# uC.net
KiCad netlist of a schematic drawn in Altium Designer
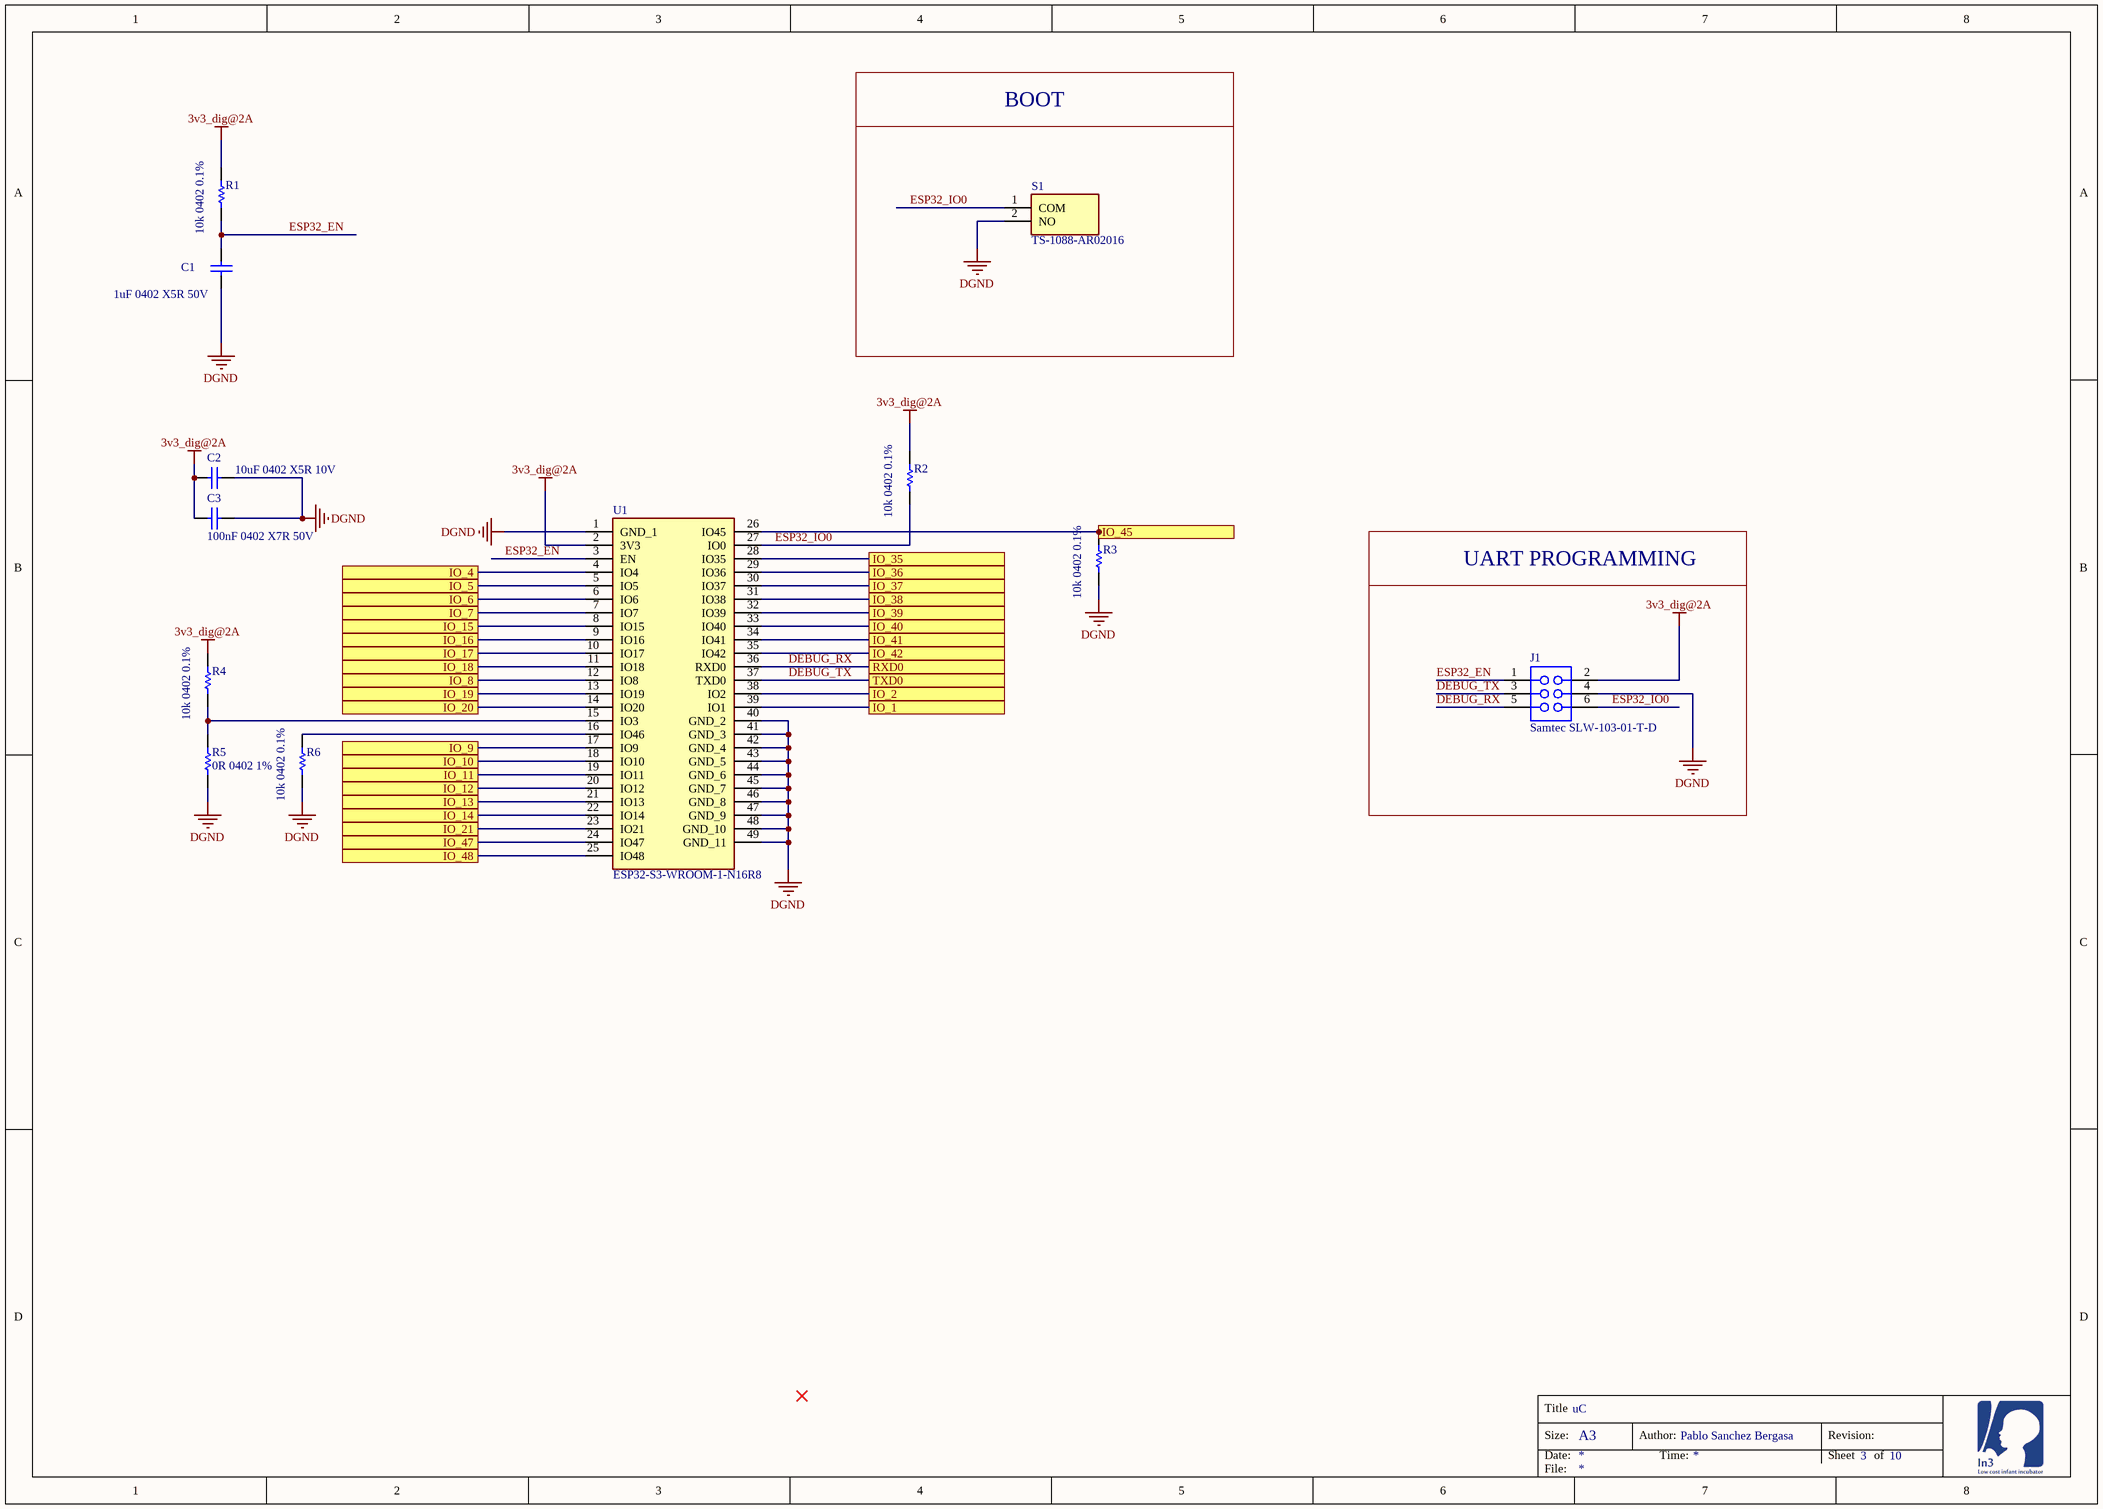
[diagram p0: uC.SchDoc]

(export (version "E")
  (design (tool "Eeschema 10.0.6"))
  (components
    (comp (ref "C1")
      (value "1uF 0402 X5R 50V")
      (footprint "CAPC1005X55X25NL5T10")
      (libsource (lib "Altium Content Vault") (part "CAP-NP-2"))
    )
    (comp (ref "C2")
      (value "10uF 0402 X5R 10V")
      (footprint "CAPC1005X55X25NL5T10")
      (libsource (lib "Altium Content Vault") (part "CAP-NP-2"))
    )
    (comp (ref "C3")
      (value "100nF 0402 X7R 50V")
      (footprint "CAPC1005X55X25NL5T10")
      (libsource (lib "Altium Content Vault") (part "CAP-NP-2"))
    )
    (comp (ref "J1")
      (value "Samtec SLW-103-01-T-D")
      (footprint "PCB-37z8hw1ej4f71bosen9e-1")
      (description "Dual Row Connector Female Samtec SLW-103-01-T-D")
      (fields (field (name "MANUFACTURER PART NUMBER") "SLW-103-01-T-D"))
      (libsource (lib "in3ator") (part "CMP-bcf575fbeff46332-1"))
    )
    (comp (ref "R1")
      (value "10k 0402 0.1%")
      (footprint "RESC1005X40X25ML05T10")
      (libsource (lib "Altium Content Vault") (part "RES"))
    )
    (comp (ref "R2")
      (value "10k 0402 0.1%")
      (footprint "RESC1005X40X25ML05T10")
      (libsource (lib "Altium Content Vault") (part "RES"))
    )
    (comp (ref "R3")
      (value "10k 0402 0.1%")
      (footprint "RESC1005X40X25ML05T10")
      (libsource (lib "Altium Content Vault") (part "RES"))
    )
    (comp (ref "R4")
      (value "10k 0402 0.1%")
      (footprint "RESC1005X40X25ML05T10")
      (libsource (lib "Altium Content Vault") (part "RES"))
    )
    (comp (ref "R5")
      (value "0R 0402 1%")
      (footprint "RESC1005X40X25ML05T10")
      (libsource (lib "Altium Content Vault") (part "RES"))
    )
    (comp (ref "R6")
      (value "10k 0402 0.1%")
      (footprint "RESC1005X40X25ML05T10")
      (libsource (lib "Altium Content Vault") (part "RES"))
    )
    (comp (ref "S1")
      (value "TS-1088-AR02016")
      (footprint "SamacSys:TS1088AR02016")
      (description "Switch")
      (libsource (lib "*") (part "TS-1088-AR02016"))
    )
    (comp (ref "U1")
      (value "ESP32-S3-WROOM-1-N16R8")
      (footprint "SamacSys:ESP32S3WROOM1N16R8")
      (description "Integrated Circuit")
      (fields (field (name "MOUSER PART NUMBER") "356-ESP32S3WRM1N16R8"))
      (libsource (lib "*") (part "ESP32-S3-WROOM-1-N16R8"))
    )
  )
  (nets
    (net (code "1") (name "/DEBUG_RX") (class "Default")
      (node (ref "J1") (pin "5") (pinfunction "5_5") (pintype "passive"))
      (node (ref "U1") (pin "36") (pinfunction "RXD0_36") (pintype "passive"))
    )
    (net (code "2") (name "/DEBUG_TX") (class "Default")
      (node (ref "J1") (pin "3") (pinfunction "3_3") (pintype "passive"))
      (node (ref "U1") (pin "37") (pinfunction "TXD0_37") (pintype "passive"))
    )
    (net (code "3") (name "/ESP32_EN") (class "Default")
      (node (ref "C1") (pin "2") (pinfunction "2_2") (pintype "passive"))
      (node (ref "J1") (pin "1") (pinfunction "1_1") (pintype "passive"))
      (node (ref "R1") (pin "1") (pinfunction "1_1") (pintype "passive"))
      (node (ref "U1") (pin "3") (pinfunction "EN_3") (pintype "passive"))
    )
    (net (code "4") (name "/ESP32_IO0") (class "Default")
      (node (ref "J1") (pin "6") (pinfunction "6_6") (pintype "passive"))
      (node (ref "R2") (pin "1") (pinfunction "1_1") (pintype "passive"))
      (node (ref "S1") (pin "1") (pinfunction "COM_1") (pintype "passive"))
      (node (ref "U1") (pin "27") (pinfunction "IO0_27") (pintype "passive"))
    )
    (net (code "5") (name "/IO_1") (class "Default")
      (node (ref "U1") (pin "39") (pinfunction "IO1_39") (pintype "passive"))
    )
    (net (code "6") (name "/IO_2") (class "Default")
      (node (ref "U1") (pin "38") (pinfunction "IO2_38") (pintype "passive"))
    )
    (net (code "7") (name "/IO_4") (class "Default")
      (node (ref "U1") (pin "4") (pinfunction "IO4_4") (pintype "passive"))
    )
    (net (code "8") (name "/IO_5") (class "Default")
      (node (ref "U1") (pin "5") (pinfunction "IO5_5") (pintype "passive"))
    )
    (net (code "9") (name "/IO_6") (class "Default")
      (node (ref "U1") (pin "6") (pinfunction "IO6_6") (pintype "passive"))
    )
    (net (code "10") (name "/IO_7") (class "Default")
      (node (ref "U1") (pin "7") (pinfunction "IO7_7") (pintype "passive"))
    )
    (net (code "11") (name "/IO_8") (class "Default")
      (node (ref "U1") (pin "12") (pinfunction "IO8_12") (pintype "passive"))
    )
    (net (code "12") (name "/IO_9") (class "Default")
      (node (ref "U1") (pin "17") (pinfunction "IO9_17") (pintype "passive"))
    )
    (net (code "13") (name "/IO_10") (class "Default")
      (node (ref "U1") (pin "18") (pinfunction "IO10_18") (pintype "passive"))
    )
    (net (code "14") (name "/IO_11") (class "Default")
      (node (ref "U1") (pin "19") (pinfunction "IO11_19") (pintype "passive"))
    )
    (net (code "15") (name "/IO_12") (class "Default")
      (node (ref "U1") (pin "20") (pinfunction "IO12_20") (pintype "passive"))
    )
    (net (code "16") (name "/IO_13") (class "Default")
      (node (ref "U1") (pin "21") (pinfunction "IO13_21") (pintype "passive"))
    )
    (net (code "17") (name "/IO_14") (class "Default")
      (node (ref "U1") (pin "22") (pinfunction "IO14_22") (pintype "passive"))
    )
    (net (code "18") (name "/IO_15") (class "Default")
      (node (ref "U1") (pin "8") (pinfunction "IO15_8") (pintype "passive"))
    )
    (net (code "19") (name "/IO_16") (class "Default")
      (node (ref "U1") (pin "9") (pinfunction "IO16_9") (pintype "passive"))
    )
    (net (code "20") (name "/IO_17") (class "Default")
      (node (ref "U1") (pin "10") (pinfunction "IO17_10") (pintype "passive"))
    )
    (net (code "21") (name "/IO_18") (class "Default")
      (node (ref "U1") (pin "11") (pinfunction "IO18_11") (pintype "passive"))
    )
    (net (code "22") (name "/IO_19") (class "Default")
      (node (ref "U1") (pin "13") (pinfunction "IO19_13") (pintype "passive"))
    )
    (net (code "23") (name "/IO_20") (class "Default")
      (node (ref "U1") (pin "14") (pinfunction "IO20_14") (pintype "passive"))
    )
    (net (code "24") (name "/IO_21") (class "Default")
      (node (ref "U1") (pin "23") (pinfunction "IO21_23") (pintype "passive"))
    )
    (net (code "25") (name "/IO_35") (class "Default")
      (node (ref "U1") (pin "28") (pinfunction "IO35_28") (pintype "passive"))
    )
    (net (code "26") (name "/IO_36") (class "Default")
      (node (ref "U1") (pin "29") (pinfunction "IO36_29") (pintype "passive"))
    )
    (net (code "27") (name "/IO_37") (class "Default")
      (node (ref "U1") (pin "30") (pinfunction "IO37_30") (pintype "passive"))
    )
    (net (code "28") (name "/IO_38") (class "Default")
      (node (ref "U1") (pin "31") (pinfunction "IO38_31") (pintype "passive"))
    )
    (net (code "29") (name "/IO_39") (class "Default")
      (node (ref "U1") (pin "32") (pinfunction "IO39_32") (pintype "passive"))
    )
    (net (code "30") (name "/IO_40") (class "Default")
      (node (ref "U1") (pin "33") (pinfunction "IO40_33") (pintype "passive"))
    )
    (net (code "31") (name "/IO_41") (class "Default")
      (node (ref "U1") (pin "34") (pinfunction "IO41_34") (pintype "passive"))
    )
    (net (code "32") (name "/IO_42") (class "Default")
      (node (ref "U1") (pin "35") (pinfunction "IO42_35") (pintype "passive"))
    )
    (net (code "33") (name "/IO_45") (class "Default")
      (node (ref "R3") (pin "2") (pinfunction "2_2") (pintype "passive"))
      (node (ref "U1") (pin "26") (pinfunction "IO45_26") (pintype "passive"))
    )
    (net (code "34") (name "/IO_47") (class "Default")
      (node (ref "U1") (pin "24") (pinfunction "IO47_24") (pintype "passive"))
    )
    (net (code "35") (name "/IO_48") (class "Default")
      (node (ref "U1") (pin "25") (pinfunction "IO48_25") (pintype "passive"))
    )
    (net (code "36") (name "3v3_dig@2A") (class "Default")
      (node (ref "C2") (pin "2") (pinfunction "2_2") (pintype "passive"))
      (node (ref "C3") (pin "2") (pinfunction "2_2") (pintype "passive"))
      (node (ref "J1") (pin "2") (pinfunction "2_2") (pintype "passive"))
      (node (ref "R1") (pin "2") (pinfunction "2_2") (pintype "passive"))
      (node (ref "R2") (pin "2") (pinfunction "2_2") (pintype "passive"))
      (node (ref "R4") (pin "2") (pinfunction "2_2") (pintype "passive"))
      (node (ref "U1") (pin "2") (pinfunction "3V3_2") (pintype "passive"))
    )
    (net (code "37") (name "DGND") (class "Default")
      (node (ref "C1") (pin "1") (pinfunction "1_1") (pintype "passive"))
      (node (ref "C2") (pin "1") (pinfunction "1_1") (pintype "passive"))
      (node (ref "C3") (pin "1") (pinfunction "1_1") (pintype "passive"))
      (node (ref "J1") (pin "4") (pinfunction "4_4") (pintype "passive"))
      (node (ref "R3") (pin "1") (pinfunction "1_1") (pintype "passive"))
      (node (ref "R5") (pin "2") (pinfunction "2_2") (pintype "passive"))
      (node (ref "R6") (pin "1") (pinfunction "1_1") (pintype "passive"))
      (node (ref "S1") (pin "2") (pinfunction "NO_2") (pintype "passive"))
      (node (ref "U1") (pin "1") (pinfunction "GND_1_1") (pintype "passive"))
      (node (ref "U1") (pin "40") (pinfunction "GND_2_40") (pintype "passive"))
      (node (ref "U1") (pin "41") (pinfunction "GND_3_41") (pintype "passive"))
      (node (ref "U1") (pin "42") (pinfunction "GND_4_42") (pintype "passive"))
      (node (ref "U1") (pin "43") (pinfunction "GND_5_43") (pintype "passive"))
      (node (ref "U1") (pin "44") (pinfunction "GND_6_44") (pintype "passive"))
      (node (ref "U1") (pin "45") (pinfunction "GND_7_45") (pintype "passive"))
      (node (ref "U1") (pin "46") (pinfunction "GND_8_46") (pintype "passive"))
      (node (ref "U1") (pin "47") (pinfunction "GND_9_47") (pintype "passive"))
      (node (ref "U1") (pin "48") (pinfunction "GND_10_48") (pintype "passive"))
      (node (ref "U1") (pin "49") (pinfunction "GND_11_49") (pintype "passive"))
    )
    (net (code "38") (name "Net-(U1-IO3)") (class "Default")
      (node (ref "R4") (pin "1") (pinfunction "1_1") (pintype "passive"))
      (node (ref "R5") (pin "1") (pinfunction "1_1") (pintype "passive"))
      (node (ref "U1") (pin "15") (pinfunction "IO3_15") (pintype "passive"))
    )
    (net (code "39") (name "Net-(U1-IO46)") (class "Default")
      (node (ref "R6") (pin "2") (pinfunction "2_2") (pintype "passive"))
      (node (ref "U1") (pin "16") (pinfunction "IO46_16") (pintype "passive"))
    )
  )
)
